# PSU1.net
KiCad netlist of a schematic drawn in EAGLE
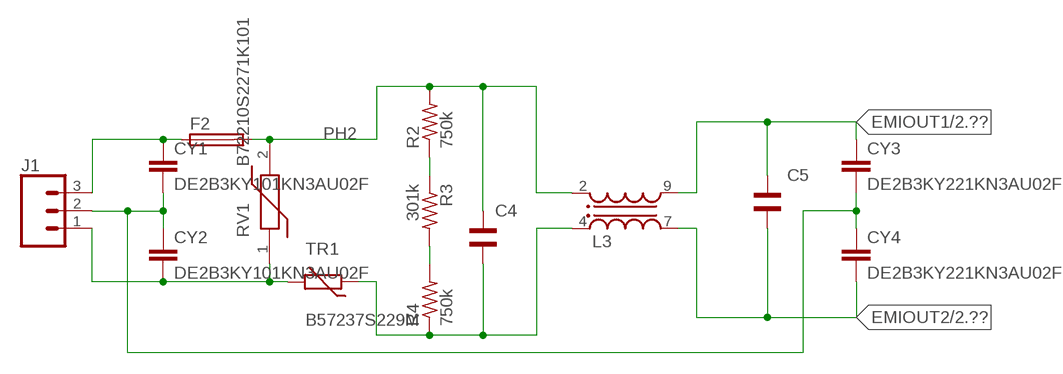
[diagram p0: schematic, sheet 1]
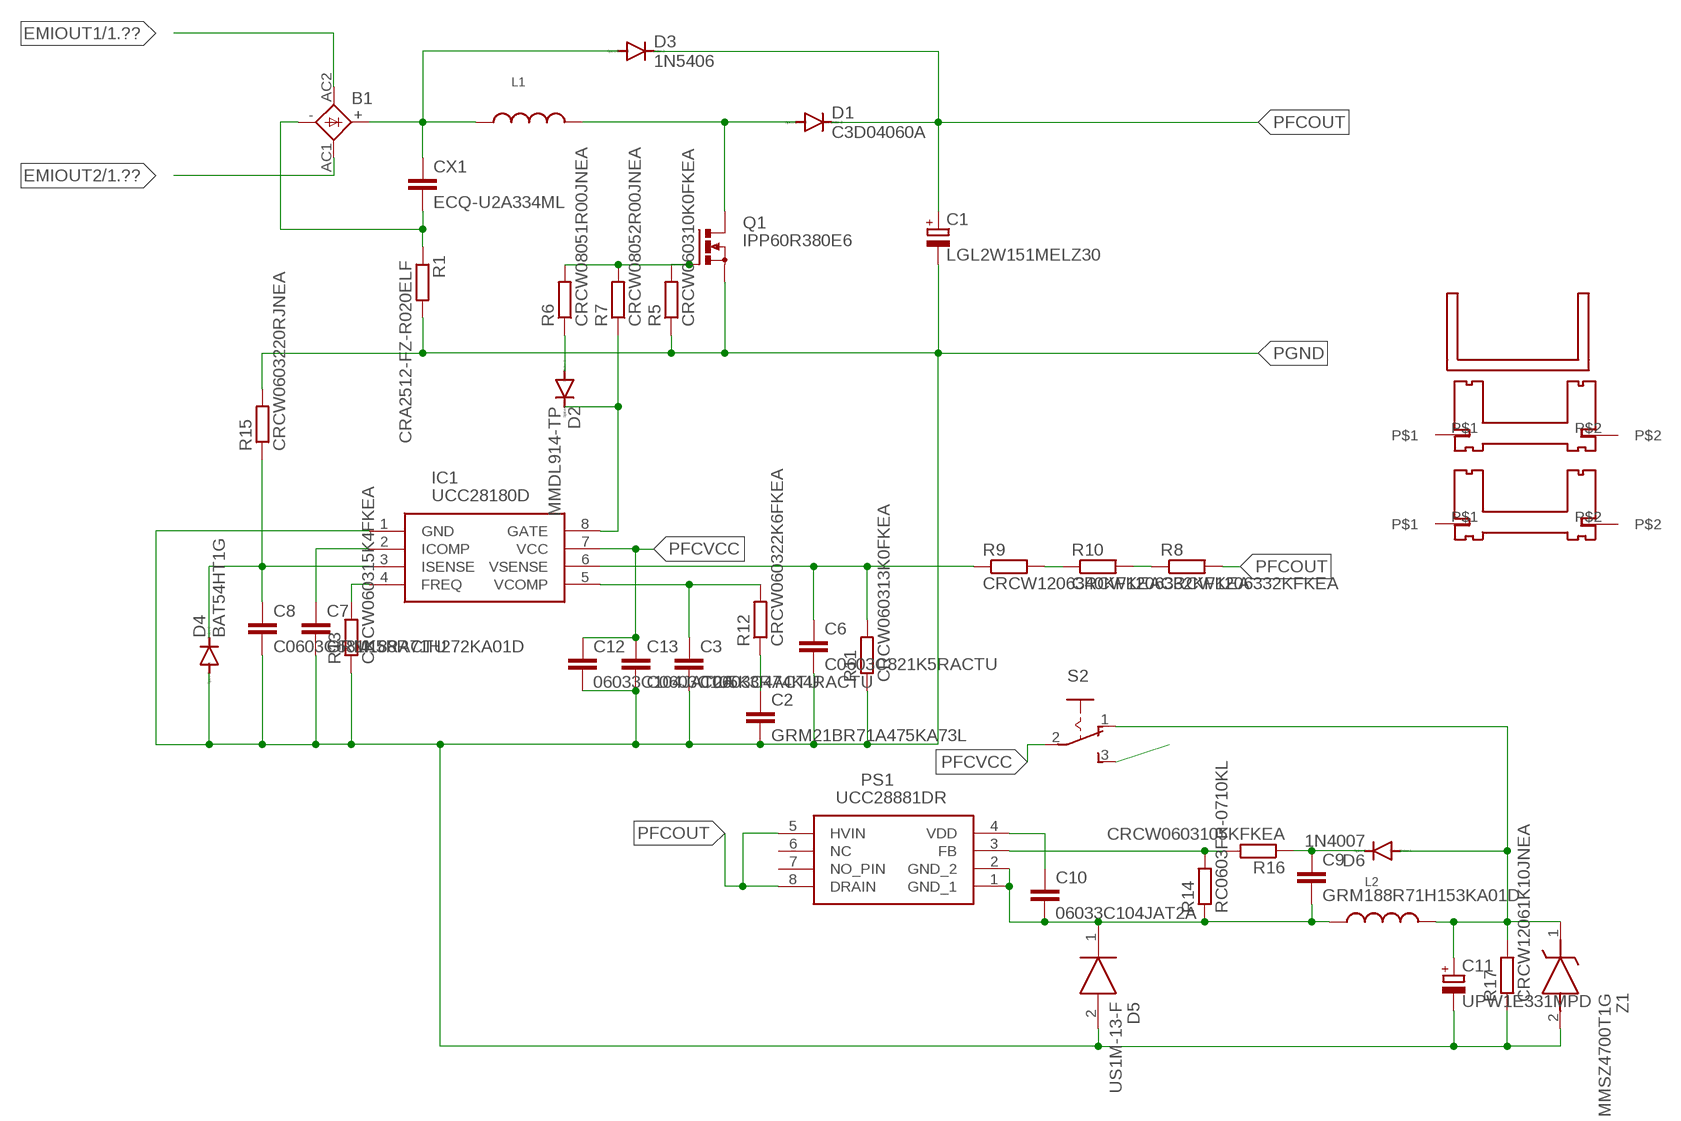
[diagram p1: schematic, sheet 2]

(export (version "E")
  (design (tool "Eeschema 10.0.6"))
  (components
    (comp (ref "C4")
      (value "WCAP-FTXX_890334025039CS")
      (footprint "eagle-import:WCAP-FTXX_15X18X14X8")
      (libsource (lib "eagle-import") (part "WCAP-FTXX_890334025039CS"))
    )
    (comp (ref "C5")
      (value "WCAP-FTXX_890334025039CS")
      (footprint "eagle-import:WCAP-FTXX_15X18X14X8")
      (libsource (lib "eagle-import") (part "WCAP-FTXX_890334025039CS"))
    )
    (comp (ref "CY1")
      (value "DE2B3KY101KN3AU02F")
      (footprint "eagle-import:YC7B5")
      (libsource (lib "eagle-import") (part "CYYC7B5"))
    )
    (comp (ref "CY2")
      (value "DE2B3KY101KN3AU02F")
      (footprint "eagle-import:YC7B5")
      (libsource (lib "eagle-import") (part "CYYC7B5"))
    )
    (comp (ref "CY3")
      (value "DE2B3KY221KN3AU02F")
      (footprint "eagle-import:YC7B5")
      (libsource (lib "eagle-import") (part "CYYC7B5"))
    )
    (comp (ref "CY4")
      (value "DE2B3KY221KN3AU02F")
      (footprint "eagle-import:YC7B5")
      (libsource (lib "eagle-import") (part "CYYC7B5"))
    )
    (comp (ref "F2")
      (value "GSH15")
      (footprint "eagle-import:GSH15")
      (fields (field (name "MPN") "64900001039"))
      (libsource (lib "eagle-import") (part "GSH15"))
    )
    (comp (ref "J1")
      (value "CONN_03-SCREW-5MM")
      (footprint "eagle-import:SCREWTERMINAL-5MM-3")
      (libsource (lib "eagle-import") (part "CONN_03-SCREW-5MM"))
    )
    (comp (ref "L3")
      (value "WE-CMB_L_744824310")
      (footprint "eagle-import:WE-CMB_L")
      (libsource (lib "eagle-import") (part "WE-CMB_L_744824310"))
    )
    (comp (ref "R2")
      (value "750k")
      (footprint "eagle-import:R1206")
      (libsource (lib "eagle-import") (part "R-US_R1206"))
    )
    (comp (ref "R3")
      (value "301k")
      (footprint "eagle-import:R1206")
      (libsource (lib "eagle-import") (part "R-US_R1206"))
    )
    (comp (ref "R4")
      (value "750k")
      (footprint "eagle-import:R1206")
      (libsource (lib "eagle-import") (part "R-US_R1206"))
    )
    (comp (ref "RV1")
      (value "B72210S2271K101")
      (footprint "eagle-import:B72210S2271K101")
      (fields (field (name "MOUSER_PART_NUMBER") "871-B72210S2271K101"))
      (libsource (lib "eagle-import") (part "B72210S2271K101"))
    )
    (comp (ref "TR1")
      (value "B57237S229M")
      (footprint "eagle-import:R-7,5")
      (libsource (lib "eagle-import") (part "THERMISTOR_R-7,5"))
    )
    (comp (ref "B1")
      (value "GBU4S")
      (footprint "eagle-import:GBU4S")
      (libsource (lib "eagle-import") (part "GBU4S"))
    )
    (comp (ref "C1")
      (value "LGL2W151MELZ30")
      (footprint "eagle-import:EB22,5D")
      (libsource (lib "eagle-import") (part "CPOL-EUE10-22.5"))
    )
    (comp (ref "C2")
      (value "GRM21BR71A475KA73L")
      (footprint "eagle-import:C0805")
      (libsource (lib "eagle-import") (part "C-EUC0805"))
    )
    (comp (ref "C3")
      (value "C0603C474K4RACTU")
      (footprint "eagle-import:C0603")
      (libsource (lib "eagle-import") (part "C-EUC0603"))
    )
    (comp (ref "C6")
      (value "C0603C821K5RACTU")
      (footprint "eagle-import:C0603")
      (libsource (lib "eagle-import") (part "C-EUC0603"))
    )
    (comp (ref "C7")
      (value "GRM188R71H272KA01D")
      (footprint "eagle-import:C0603")
      (libsource (lib "eagle-import") (part "C-EUC0603"))
    )
    (comp (ref "C8")
      (value "C0603C681K5RACTU")
      (footprint "eagle-import:C0603")
      (libsource (lib "eagle-import") (part "C-EUC0603"))
    )
    (comp (ref "C9")
      (value "GRM188R71H153KA01D")
      (footprint "eagle-import:C0603")
      (libsource (lib "eagle-import") (part "C-EUC0603"))
    )
    (comp (ref "C10")
      (value "06033C104JAT2A")
      (footprint "eagle-import:C0603")
      (libsource (lib "eagle-import") (part "C-EUC0603"))
    )
    (comp (ref "C11")
      (value "UPW1E331MPD")
      (footprint "eagle-import:E5-10,5")
      (libsource (lib "eagle-import") (part "CPOL-EUE5-10.5"))
    )
    (comp (ref "C12")
      (value "06033C104JAT2A")
      (footprint "eagle-import:C0603")
      (libsource (lib "eagle-import") (part "C-EUC0603"))
    )
    (comp (ref "C13")
      (value "C0603C105K3RACTU")
      (footprint "eagle-import:C0603")
      (libsource (lib "eagle-import") (part "C-EUC0603"))
    )
    (comp (ref "CX1")
      (value "ECQ-U2A334ML")
      (footprint "eagle-import:XC15B10")
      (libsource (lib "eagle-import") (part "CXXC15B10"))
    )
    (comp (ref "D1")
      (value "C3D04060A")
      (footprint "eagle-import:TO220ACS")
      (libsource (lib "eagle-import") (part "DIODE-TO220V"))
    )
    (comp (ref "D2")
      (value "MMDL914-TP")
      (footprint "eagle-import:SOD323-R")
      (libsource (lib "eagle-import") (part "DIODE-SOD323-R"))
    )
    (comp (ref "D3")
      (value "1N5406")
      (footprint "eagle-import:DO201-15")
      (libsource (lib "eagle-import") (part "DIODE-DO201-15"))
    )
    (comp (ref "D4")
      (value "BAT54HT1G")
      (footprint "eagle-import:SOD323-R")
      (libsource (lib "eagle-import") (part "DIODE-SOD323-R"))
    )
    (comp (ref "D5")
      (value "US1M-13-F")
      (footprint "eagle-import:SODFL5226X240N")
      (fields (field (name "MOUSER_PART_NUMBER") "621-US1M-F") (field (name "RS_PART_NUMBER") "7385074P"))
      (libsource (lib "eagle-import") (part "US1M-13-F"))
    )
    (comp (ref "D6")
      (value "1N4007")
      (footprint "eagle-import:DO41-7.6")
      (libsource (lib "eagle-import") (part "DIODE-DO41-7.6"))
    )
    (comp (ref "IC1")
      (value "UCC28180D")
      (footprint "eagle-import:SOIC127P600X175-8N")
      (fields (field (name "MOUSER_PART_NUMBER") "595-UCC28180D"))
      (libsource (lib "eagle-import") (part "UCC28180D"))
    )
    (comp (ref "L1")
      (value "WE-HCF_ROUND_74437529203471")
      (footprint "eagle-import:WE-HCF_ROUND")
      (libsource (lib "eagle-import") (part "WE-HCF_ROUND_74437529203471"))
    )
    (comp (ref "L2")
      (value "WE-TIS_1111_7447471102")
      (footprint "eagle-import:WE-TIS_1111")
      (libsource (lib "eagle-import") (part "WE-TIS_1111_7447471102"))
    )
    (comp (ref "PS1")
      (value "UCC28881DR")
      (footprint "eagle-import:SOIC127P600X175-8N")
      (fields (field (name "MOUSER_PART_NUMBER") "595-UCC28881DR"))
      (libsource (lib "eagle-import") (part "UCC28881DR"))
    )
    (comp (ref "Q1")
      (value "IPP60R380E6")
      (footprint "eagle-import:TO220BV")
      (libsource (lib "eagle-import") (part "PMOSFET_NTO220BV"))
    )
    (comp (ref "R1")
      (value "CRA2512-FZ-R020ELF")
      (footprint "eagle-import:R2512W")
      (libsource (lib "eagle-import") (part "R-EU_R2512W"))
    )
    (comp (ref "R5")
      (value "CRCW060310K0FKEA")
      (footprint "eagle-import:R0603")
      (libsource (lib "eagle-import") (part "R-EU_R0603"))
    )
    (comp (ref "R6")
      (value "CRCW08051R00JNEA")
      (footprint "eagle-import:R0805")
      (libsource (lib "eagle-import") (part "R-EU_R0805"))
    )
    (comp (ref "R7")
      (value "CRCW08052R00JNEA")
      (footprint "eagle-import:R0805")
      (libsource (lib "eagle-import") (part "R-EU_R0805"))
    )
    (comp (ref "R8")
      (value "CRCW1206332KFKEA")
      (footprint "eagle-import:R1206")
      (libsource (lib "eagle-import") (part "R-EU_R1206"))
    )
    (comp (ref "R9")
      (value "CRCW1206340KFKEA")
      (footprint "eagle-import:R1206")
      (libsource (lib "eagle-import") (part "R-EU_R1206"))
    )
    (comp (ref "R10")
      (value "CRCW1206332KFKEA")
      (footprint "eagle-import:R1206")
      (libsource (lib "eagle-import") (part "R-EU_R1206"))
    )
    (comp (ref "R11")
      (value "CRCW060313K0FKEA")
      (footprint "eagle-import:R0603")
      (libsource (lib "eagle-import") (part "R-EU_R0603"))
    )
    (comp (ref "R12")
      (value "CRCW060322K6FKEA")
      (footprint "eagle-import:R0603")
      (libsource (lib "eagle-import") (part "R-EU_R0603"))
    )
    (comp (ref "R13")
      (value "CRCW060315K4FKEA")
      (footprint "eagle-import:R0603")
      (libsource (lib "eagle-import") (part "R-EU_R0603"))
    )
    (comp (ref "R14")
      (value "RC0603FR-0710KL")
      (footprint "eagle-import:R0805")
      (libsource (lib "eagle-import") (part "R-EU_R0805"))
    )
    (comp (ref "R15")
      (value "CRCW0603220RJNEA")
      (footprint "eagle-import:R0603")
      (libsource (lib "eagle-import") (part "R-EU_R0603"))
    )
    (comp (ref "R16")
      (value "CRCW0603105KFKEA")
      (footprint "eagle-import:R0805")
      (libsource (lib "eagle-import") (part "R-EU_R0805"))
    )
    (comp (ref "R17")
      (value "CRCW12061K10JNEA")
      (footprint "eagle-import:R1206")
      (libsource (lib "eagle-import") (part "R-EU_R1206"))
    )
    (comp (ref "S2")
      (value "255SB")
      (footprint "eagle-import:255SB")
      (libsource (lib "eagle-import") (part "255SB"))
    )
    (comp (ref "U$1")
      (value "HEAT001")
      (footprint "eagle-import:HEAT01")
      (libsource (lib "eagle-import") (part "HEAT001"))
    )
    (comp (ref "U$2")
      (value "HEAT002")
      (footprint "eagle-import:HEAT02")
      (libsource (lib "eagle-import") (part "HEAT002"))
    )
    (comp (ref "U$3")
      (value "HEAT001")
      (footprint "eagle-import:HEAT01")
      (libsource (lib "eagle-import") (part "HEAT001"))
    )
    (comp (ref "Z1")
      (value "MMSZ4700T1G")
      (footprint "eagle-import:SOD3716X135N")
      (fields
        (field (name "MOUSER_PART_NUMBER") "863-MMSZ4700T1G")
        (field (name "RS_PART_NUMBER") "8021853P")
      )
      (libsource (lib "eagle-import") (part "MMSZ4700T1G"))
    )
  )
  (nets
    (net (code "1") (name "EMIOUT1") (class "Default")
      (node (ref "B1") (pin "AC2") (pinfunction "AC1_AC2") (pintype "passive"))
      (node (ref "C5") (pin "2") (pinfunction "2_2") (pintype "passive"))
      (node (ref "CY3") (pin "1") (pinfunction "1_1") (pintype "passive"))
      (node (ref "L3") (pin "9") (pinfunction "3_9") (pintype "passive"))
    )
    (net (code "2") (name "EMIOUT2") (class "Default")
      (node (ref "B1") (pin "AC1") (pinfunction "AC2_AC1") (pintype "passive"))
      (node (ref "C5") (pin "1") (pinfunction "1_1") (pintype "passive"))
      (node (ref "CY4") (pin "2") (pinfunction "2_2") (pintype "passive"))
      (node (ref "L3") (pin "7") (pinfunction "2_7") (pintype "passive"))
    )
    (net (code "3") (name "Net-(B1-Pad+)") (class "Default")
      (node (ref "B1") (pin "+") (pinfunction "+_+") (pintype "passive"))
      (node (ref "CX1") (pin "1") (pinfunction "1_1") (pintype "passive"))
      (node (ref "D3") (pin "A") (pinfunction "A_A") (pintype "passive"))
      (node (ref "L1") (pin "1") (pinfunction "1_1") (pintype "passive"))
    )
    (net (code "4") (name "Net-(B1-Pad-)") (class "Default")
      (node (ref "B1") (pin "-") (pinfunction "-_-") (pintype "passive"))
      (node (ref "CX1") (pin "2") (pinfunction "2_2") (pintype "passive"))
      (node (ref "R1") (pin "1") (pinfunction "1_1") (pintype "passive"))
    )
    (net (code "5") (name "Net-(C2-Pad1)") (class "Default")
      (node (ref "C2") (pin "1") (pinfunction "1_1") (pintype "passive"))
      (node (ref "R12") (pin "1") (pinfunction "1_1") (pintype "passive"))
    )
    (net (code "6") (name "Net-(C9-Pad1)") (class "Default")
      (node (ref "C9") (pin "1") (pinfunction "1_1") (pintype "passive"))
      (node (ref "D6") (pin "C") (pinfunction "C_C") (pintype "passive"))
      (node (ref "R16") (pin "1") (pinfunction "1_1") (pintype "passive"))
    )
    (net (code "7") (name "Net-(CY1-Pad1)") (class "Default")
      (node (ref "CY1") (pin "1") (pinfunction "1_1") (pintype "passive"))
      (node (ref "F2") (pin "1") (pinfunction "1_1") (pintype "passive"))
      (node (ref "J1") (pin "3") (pinfunction "3_3") (pintype "passive"))
    )
    (net (code "8") (name "Net-(CY1-Pad2)") (class "Default")
      (node (ref "CY1") (pin "2") (pinfunction "2_2") (pintype "passive"))
      (node (ref "CY2") (pin "1") (pinfunction "1_1") (pintype "passive"))
      (node (ref "CY3") (pin "2") (pinfunction "2_2") (pintype "passive"))
      (node (ref "CY4") (pin "1") (pinfunction "1_1") (pintype "passive"))
      (node (ref "J1") (pin "2") (pinfunction "2_2") (pintype "passive"))
    )
    (net (code "9") (name "Net-(CY2-Pad2)") (class "Default")
      (node (ref "CY2") (pin "2") (pinfunction "2_2") (pintype "passive"))
      (node (ref "J1") (pin "1") (pinfunction "1_1") (pintype "passive"))
      (node (ref "RV1") (pin "1") (pinfunction "1_1") (pintype "bidirectional"))
      (node (ref "TR1") (pin "2") (pinfunction "2_2") (pintype "passive"))
    )
    (net (code "10") (name "Net-(D1-PadA)") (class "Default")
      (node (ref "D1") (pin "A") (pinfunction "A_A") (pintype "passive"))
      (node (ref "L1") (pin "2") (pinfunction "2_2") (pintype "passive"))
      (node (ref "Q1") (pin "D") (pinfunction "D_D") (pintype "passive"))
    )
    (net (code "11") (name "Net-(D2-PadA)") (class "Default")
      (node (ref "D2") (pin "A") (pinfunction "A_A") (pintype "passive"))
      (node (ref "R6") (pin "1") (pinfunction "1_1") (pintype "passive"))
    )
    (net (code "12") (name "Net-(D5-K)") (class "Default")
      (node (ref "C10") (pin "2") (pinfunction "2_2") (pintype "passive"))
      (node (ref "C9") (pin "2") (pinfunction "2_2") (pintype "passive"))
      (node (ref "D5") (pin "1") (pinfunction "K_1") (pintype "bidirectional"))
      (node (ref "L2") (pin "1") (pinfunction "1_1") (pintype "passive"))
      (node (ref "PS1") (pin "1") (pinfunction "GND_1_1") (pintype "power_in"))
      (node (ref "PS1") (pin "2") (pinfunction "GND_2_2") (pintype "power_in"))
      (node (ref "R14") (pin "1") (pinfunction "1_1") (pintype "passive"))
    )
    (net (code "13") (name "Net-(IC1-FREQ)") (class "Default")
      (node (ref "IC1") (pin "4") (pinfunction "FREQ_4") (pintype "bidirectional"))
      (node (ref "R13") (pin "2") (pinfunction "2_2") (pintype "passive"))
    )
    (net (code "14") (name "Net-(IC1-GATE)") (class "Default")
      (node (ref "D2") (pin "C") (pinfunction "C_C") (pintype "passive"))
      (node (ref "IC1") (pin "8") (pinfunction "GATE_8") (pintype "bidirectional"))
      (node (ref "R7") (pin "1") (pinfunction "1_1") (pintype "passive"))
    )
    (net (code "15") (name "Net-(IC1-ICOMP)") (class "Default")
      (node (ref "C7") (pin "1") (pinfunction "1_1") (pintype "passive"))
      (node (ref "IC1") (pin "2") (pinfunction "ICOMP_2") (pintype "bidirectional"))
    )
    (net (code "16") (name "Net-(IC1-ISENSE)") (class "Default")
      (node (ref "C8") (pin "1") (pinfunction "1_1") (pintype "passive"))
      (node (ref "D4") (pin "C") (pinfunction "C_C") (pintype "passive"))
      (node (ref "IC1") (pin "3") (pinfunction "ISENSE_3") (pintype "bidirectional"))
      (node (ref "R15") (pin "1") (pinfunction "1_1") (pintype "passive"))
    )
    (net (code "17") (name "Net-(IC1-VCOMP)") (class "Default")
      (node (ref "C3") (pin "1") (pinfunction "1_1") (pintype "passive"))
      (node (ref "IC1") (pin "5") (pinfunction "VCOMP_5") (pintype "bidirectional"))
      (node (ref "R12") (pin "2") (pinfunction "2_2") (pintype "passive"))
    )
    (net (code "18") (name "Net-(IC1-VSENSE)") (class "Default")
      (node (ref "C6") (pin "1") (pinfunction "1_1") (pintype "passive"))
      (node (ref "IC1") (pin "6") (pinfunction "VSENSE_6") (pintype "bidirectional"))
      (node (ref "R11") (pin "2") (pinfunction "2_2") (pintype "passive"))
      (node (ref "R9") (pin "1") (pinfunction "1_1") (pintype "passive"))
    )
    (net (code "19") (name "Net-(L3-1)") (class "Default")
      (node (ref "C4") (pin "2") (pinfunction "2_2") (pintype "passive"))
      (node (ref "L3") (pin "4") (pinfunction "1_4") (pintype "passive"))
      (node (ref "R4") (pin "1") (pinfunction "1_1") (pintype "passive"))
      (node (ref "TR1") (pin "1") (pinfunction "1_1") (pintype "passive"))
    )
    (net (code "20") (name "Net-(PS1-FB)") (class "Default")
      (node (ref "PS1") (pin "3") (pinfunction "FB_3") (pintype "input"))
      (node (ref "R14") (pin "2") (pinfunction "2_2") (pintype "passive"))
      (node (ref "R16") (pin "2") (pinfunction "2_2") (pintype "passive"))
    )
    (net (code "21") (name "Net-(PS1-VDD)") (class "Default")
      (node (ref "C10") (pin "1") (pinfunction "1_1") (pintype "passive"))
      (node (ref "PS1") (pin "4") (pinfunction "VDD_4") (pintype "power_in"))
    )
    (net (code "22") (name "Net-(Q1-PadG)") (class "Default")
      (node (ref "Q1") (pin "G") (pinfunction "G_G") (pintype "passive"))
      (node (ref "R5") (pin "2") (pinfunction "2_2") (pintype "passive"))
      (node (ref "R6") (pin "2") (pinfunction "2_2") (pintype "passive"))
      (node (ref "R7") (pin "2") (pinfunction "2_2") (pintype "passive"))
    )
    (net (code "23") (name "Net-(R2-Pad1)") (class "Default")
      (node (ref "R2") (pin "1") (pinfunction "1_1") (pintype "passive"))
      (node (ref "R3") (pin "1") (pinfunction "1_1") (pintype "passive"))
    )
    (net (code "24") (name "Net-(R3-Pad2)") (class "Default")
      (node (ref "R3") (pin "2") (pinfunction "2_2") (pintype "passive"))
      (node (ref "R4") (pin "2") (pinfunction "2_2") (pintype "passive"))
    )
    (net (code "25") (name "Net-(R10-Pad1)") (class "Default")
      (node (ref "R10") (pin "1") (pinfunction "1_1") (pintype "passive"))
      (node (ref "R9") (pin "2") (pinfunction "2_2") (pintype "passive"))
    )
    (net (code "26") (name "Net-(R10-Pad2)") (class "Default")
      (node (ref "R10") (pin "2") (pinfunction "2_2") (pintype "passive"))
      (node (ref "R8") (pin "1") (pinfunction "1_1") (pintype "passive"))
    )
    (net (code "27") (name "Net-(S2-O)") (class "Default")
      (node (ref "C11") (pin "+") (pinfunction "+_+") (pintype "passive"))
      (node (ref "D6") (pin "A") (pinfunction "A_A") (pintype "passive"))
      (node (ref "L2") (pin "2") (pinfunction "2_2") (pintype "passive"))
      (node (ref "R17") (pin "2") (pinfunction "2_2") (pintype "passive"))
      (node (ref "S2") (pin "1") (pinfunction "O_1") (pintype "passive"))
      (node (ref "Z1") (pin "1") (pinfunction "K_1") (pintype "bidirectional"))
    )
    (net (code "28") (name "PFCOUT") (class "Default")
      (node (ref "C1") (pin "+") (pinfunction "+_+") (pintype "passive"))
      (node (ref "D1") (pin "C") (pinfunction "C_C") (pintype "passive"))
      (node (ref "D3") (pin "C") (pinfunction "C_C") (pintype "passive"))
      (node (ref "PS1") (pin "5") (pinfunction "HVIN_5") (pintype "power_in"))
      (node (ref "PS1") (pin "8") (pinfunction "DRAIN_8") (pintype "bidirectional"))
      (node (ref "R8") (pin "2") (pinfunction "2_2") (pintype "passive"))
    )
    (net (code "29") (name "PFCVCC") (class "Default")
      (node (ref "C12") (pin "1") (pinfunction "1_1") (pintype "passive"))
      (node (ref "C13") (pin "1") (pinfunction "1_1") (pintype "passive"))
      (node (ref "IC1") (pin "7") (pinfunction "VCC_7") (pintype "bidirectional"))
      (node (ref "S2") (pin "2") (pinfunction "P_2") (pintype "passive"))
    )
    (net (code "30") (name "PGND") (class "Default")
      (node (ref "C1") (pin "-") (pinfunction "-_-") (pintype "passive"))
      (node (ref "C11") (pin "-") (pinfunction "-_-") (pintype "passive"))
      (node (ref "C12") (pin "2") (pinfunction "2_2") (pintype "passive"))
      (node (ref "C13") (pin "2") (pinfunction "2_2") (pintype "passive"))
      (node (ref "C2") (pin "2") (pinfunction "2_2") (pintype "passive"))
      (node (ref "C3") (pin "2") (pinfunction "2_2") (pintype "passive"))
      (node (ref "C6") (pin "2") (pinfunction "2_2") (pintype "passive"))
      (node (ref "C7") (pin "2") (pinfunction "2_2") (pintype "passive"))
      (node (ref "C8") (pin "2") (pinfunction "2_2") (pintype "passive"))
      (node (ref "D4") (pin "A") (pinfunction "A_A") (pintype "passive"))
      (node (ref "D5") (pin "2") (pinfunction "A_2") (pintype "bidirectional"))
      (node (ref "IC1") (pin "1") (pinfunction "GND_1") (pintype "bidirectional"))
      (node (ref "Q1") (pin "S") (pinfunction "S_S") (pintype "passive"))
      (node (ref "R1") (pin "2") (pinfunction "2_2") (pintype "passive"))
      (node (ref "R11") (pin "1") (pinfunction "1_1") (pintype "passive"))
      (node (ref "R13") (pin "1") (pinfunction "1_1") (pintype "passive"))
      (node (ref "R15") (pin "2") (pinfunction "2_2") (pintype "passive"))
      (node (ref "R17") (pin "1") (pinfunction "1_1") (pintype "passive"))
      (node (ref "R5") (pin "1") (pinfunction "1_1") (pintype "passive"))
      (node (ref "Z1") (pin "2") (pinfunction "A_2") (pintype "bidirectional"))
    )
    (net (code "31") (name "PH2") (class "Default")
      (node (ref "C4") (pin "1") (pinfunction "1_1") (pintype "passive"))
      (node (ref "F2") (pin "2") (pinfunction "2_2") (pintype "passive"))
      (node (ref "L3") (pin "2") (pinfunction "4_2") (pintype "passive"))
      (node (ref "R2") (pin "2") (pinfunction "2_2") (pintype "passive"))
      (node (ref "RV1") (pin "2") (pinfunction "2_2") (pintype "bidirectional"))
    )
    (net (code "32") (name "unconnected-(PS1-NC-Pad6)") (class "Default")
      (node (ref "PS1") (pin "6") (pinfunction "NC_6") (pintype "no_connect"))
    )
    (net (code "33") (name "unconnected-(PS1-NO_PIN-Pad7)") (class "Default")
      (node (ref "PS1") (pin "7") (pinfunction "NO_PIN_7") (pintype "bidirectional"))
    )
    (net (code "34") (name "unconnected-(S2-S-Pad3)") (class "Default")
      (node (ref "S2") (pin "3") (pinfunction "S_3") (pintype "passive"))
    )
    (net (code "35") (name "unconnected-(U$1-PadP$1)") (class "Default")
      (node (ref "U$1") (pin "P$1") (pinfunction "P$1_P$1") (pintype "bidirectional"))
    )
    (net (code "36") (name "unconnected-(U$1-PadP$2)") (class "Default")
      (node (ref "U$1") (pin "P$2") (pinfunction "P$2_P$2") (pintype "bidirectional"))
    )
    (net (code "37") (name "unconnected-(U$3-PadP$1)") (class "Default")
      (node (ref "U$3") (pin "P$1") (pinfunction "P$1_P$1") (pintype "bidirectional"))
    )
    (net (code "38") (name "unconnected-(U$3-PadP$2)") (class "Default")
      (node (ref "U$3") (pin "P$2") (pinfunction "P$2_P$2") (pintype "bidirectional"))
    )
  )
)
